# Motor_Driver_Mike.net
KiCad netlist of a schematic drawn in EAGLE
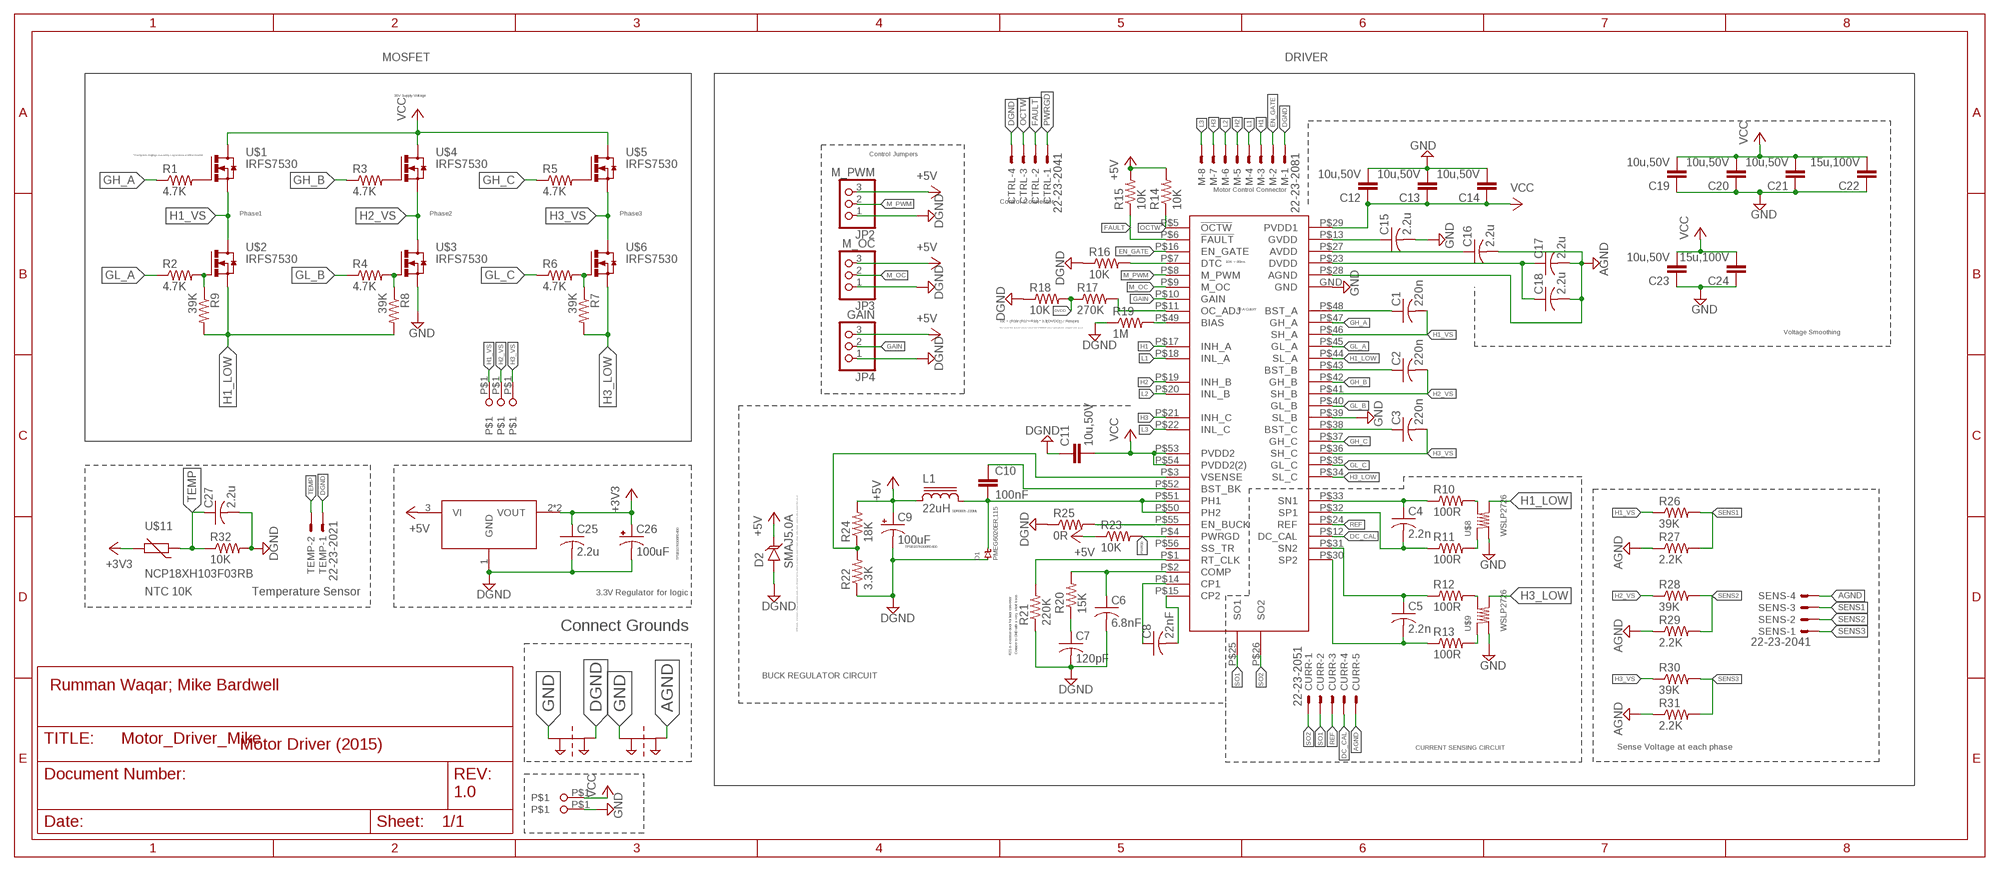
[diagram p0: schematic, sheet 1]

(export (version "E")
  (design (tool "Eeschema 10.0.6"))
  (components
    (comp (ref "C1")
      (value "220n")
      (footprint "eagle-import:C0805")
      (libsource (lib "eagle-import") (part "C-USC0805"))
    )
    (comp (ref "C2")
      (value "220n")
      (footprint "eagle-import:C0805")
      (libsource (lib "eagle-import") (part "C-USC0805"))
    )
    (comp (ref "C3")
      (value "220n")
      (footprint "eagle-import:C0805")
      (libsource (lib "eagle-import") (part "C-USC0805"))
    )
    (comp (ref "C4")
      (value "2.2n")
      (footprint "eagle-import:C0603")
      (libsource (lib "eagle-import") (part "C-USC0603"))
    )
    (comp (ref "C5")
      (value "2.2n")
      (footprint "eagle-import:C0603")
      (libsource (lib "eagle-import") (part "C-USC0603"))
    )
    (comp (ref "C6")
      (value "6.8nF")
      (footprint "eagle-import:C0603")
      (libsource (lib "eagle-import") (part "C-USC0603"))
    )
    (comp (ref "C7")
      (value "120pF")
      (footprint "eagle-import:C0603")
      (libsource (lib "eagle-import") (part "C-USC0603"))
    )
    (comp (ref "C8")
      (value "22nF")
      (footprint "eagle-import:C0603")
      (libsource (lib "eagle-import") (part "C-USC0603"))
    )
    (comp (ref "C9")
      (value "100uF")
      (footprint "eagle-import:EIA3528-KIT")
      (libsource (lib "eagle-import") (part "CAP_POL3528-KIT"))
    )
    (comp (ref "C10")
      (value "100nF")
      (footprint "eagle-import:0805")
      (libsource (lib "eagle-import") (part "CAP0805"))
    )
    (comp (ref "C11")
      (value "10u,50V")
      (footprint "eagle-import:1206")
      (libsource (lib "eagle-import") (part "CAP1206"))
    )
    (comp (ref "C12")
      (value "10u,50V")
      (footprint "eagle-import:1206")
      (libsource (lib "eagle-import") (part "CAP1206"))
    )
    (comp (ref "C13")
      (value "10u,50V")
      (footprint "eagle-import:1206")
      (libsource (lib "eagle-import") (part "CAP1206"))
    )
    (comp (ref "C14")
      (value "10u,50V")
      (footprint "eagle-import:1206")
      (libsource (lib "eagle-import") (part "CAP1206"))
    )
    (comp (ref "C15")
      (value "2.2u")
      (footprint "eagle-import:C0805")
      (libsource (lib "eagle-import") (part "C-USC0805"))
    )
    (comp (ref "C16")
      (value "2.2u")
      (footprint "eagle-import:C0805")
      (libsource (lib "eagle-import") (part "C-USC0805"))
    )
    (comp (ref "C17")
      (value "2.2u")
      (footprint "eagle-import:C0805")
      (libsource (lib "eagle-import") (part "C-USC0805"))
    )
    (comp (ref "C18")
      (value "2.2u")
      (footprint "eagle-import:C0805")
      (libsource (lib "eagle-import") (part "C-USC0805"))
    )
    (comp (ref "C19")
      (value "10u,50V")
      (footprint "eagle-import:1206")
      (libsource (lib "eagle-import") (part "CAP1206"))
    )
    (comp (ref "C20")
      (value "10u,50V")
      (footprint "eagle-import:1206")
      (libsource (lib "eagle-import") (part "CAP1206"))
    )
    (comp (ref "C21")
      (value "10u,50V")
      (footprint "eagle-import:1206")
      (libsource (lib "eagle-import") (part "CAP1206"))
    )
    (comp (ref "C22")
      (value "15u,100V")
      (footprint "eagle-import:C2220K")
      (libsource (lib "eagle-import") (part "C-EUC2220K"))
    )
    (comp (ref "C23")
      (value "10u,50V")
      (footprint "eagle-import:1206")
      (libsource (lib "eagle-import") (part "CAP1206"))
    )
    (comp (ref "C24")
      (value "15u,100V")
      (footprint "eagle-import:C2220K")
      (libsource (lib "eagle-import") (part "C-EUC2220K"))
    )
    (comp (ref "C25")
      (value "2.2u")
      (footprint "eagle-import:C0805")
      (libsource (lib "eagle-import") (part "C-USC0805"))
    )
    (comp (ref "C26")
      (value "100uF")
      (footprint "eagle-import:EIA3528-KIT")
      (libsource (lib "eagle-import") (part "CAP_POL3528-KIT"))
    )
    (comp (ref "C27")
      (value "2.2u")
      (footprint "eagle-import:C0805")
      (libsource (lib "eagle-import") (part "C-USC0805"))
    )
    (comp (ref "CTRL")
      (value "22-23-2041")
      (footprint "eagle-import:22-23-2041")
      (fields (field (name "MF") "MOLEX"))
      (libsource (lib "eagle-import") (part "22-23-2041"))
    )
    (comp (ref "CURR")
      (value "22-23-2051")
      (footprint "eagle-import:22-23-2051")
      (fields (field (name "MF") "MOLEX"))
      (libsource (lib "eagle-import") (part "22-23-2051"))
    )
    (comp (ref "D1")
      (value "PMEG6020ER,115")
      (footprint "eagle-import:SOD123W")
      (libsource (lib "eagle-import") (part "DIODE[SCHOTKY]-SOD123W"))
    )
    (comp (ref "D2")
      (value "SMAJ5.0A")
      (footprint "eagle-import:SMA-DIODE")
      (libsource (lib "eagle-import") (part "TVSSMA"))
    )
    (comp (ref "JP2")
      (value "M_PWM")
      (footprint "eagle-import:1X03")
      (libsource (lib "eagle-import") (part "PINHD-1X3"))
    )
    (comp (ref "JP3")
      (value "M_OC")
      (footprint "eagle-import:1X03")
      (libsource (lib "eagle-import") (part "PINHD-1X3"))
    )
    (comp (ref "JP4")
      (value "GAIN")
      (footprint "eagle-import:1X03")
      (libsource (lib "eagle-import") (part "PINHD-1X3"))
    )
    (comp (ref "L1")
      (value "22uH")
      (footprint "eagle-import:SDR0805")
      (libsource (lib "eagle-import") (part "SDR0805"))
    )
    (comp (ref "M")
      (value "22-23-2081")
      (footprint "eagle-import:22-23-2081")
      (fields (field (name "MF") "MOLEX"))
      (libsource (lib "eagle-import") (part "22-23-2081"))
    )
    (comp (ref "PT1")
      (value "2PT_GND_TIE")
      (footprint "eagle-import:2PT_GND_TIE")
      (libsource (lib "eagle-import") (part "2PT_GND_TIE"))
    )
    (comp (ref "PT2")
      (value "2PT_GND_TIE")
      (footprint "eagle-import:2PT_GND_TIE")
      (libsource (lib "eagle-import") (part "2PT_GND_TIE"))
    )
    (comp (ref "R1")
      (value "4.7K")
      (footprint "eagle-import:R0603")
      (libsource (lib "eagle-import") (part "R-US_R0603"))
    )
    (comp (ref "R2")
      (value "4.7K")
      (footprint "eagle-import:R0603")
      (libsource (lib "eagle-import") (part "R-US_R0603"))
    )
    (comp (ref "R3")
      (value "4.7K")
      (footprint "eagle-import:R0603")
      (libsource (lib "eagle-import") (part "R-US_R0603"))
    )
    (comp (ref "R4")
      (value "4.7K")
      (footprint "eagle-import:R0603")
      (libsource (lib "eagle-import") (part "R-US_R0603"))
    )
    (comp (ref "R5")
      (value "4.7K")
      (footprint "eagle-import:R0603")
      (libsource (lib "eagle-import") (part "R-US_R0603"))
    )
    (comp (ref "R6")
      (value "4.7K")
      (footprint "eagle-import:R0603")
      (libsource (lib "eagle-import") (part "R-US_R0603"))
    )
    (comp (ref "R7")
      (value "39K")
      (footprint "eagle-import:R0603")
      (libsource (lib "eagle-import") (part "R-US_R0603"))
    )
    (comp (ref "R8")
      (value "39K")
      (footprint "eagle-import:R0603")
      (libsource (lib "eagle-import") (part "R-US_R0603"))
    )
    (comp (ref "R9")
      (value "39K")
      (footprint "eagle-import:R0603")
      (libsource (lib "eagle-import") (part "R-US_R0603"))
    )
    (comp (ref "R10")
      (value "100R")
      (footprint "eagle-import:R0603")
      (libsource (lib "eagle-import") (part "R-US_R0603"))
    )
    (comp (ref "R11")
      (value "100R")
      (footprint "eagle-import:R0603")
      (libsource (lib "eagle-import") (part "R-US_R0603"))
    )
    (comp (ref "R12")
      (value "100R")
      (footprint "eagle-import:R0603")
      (libsource (lib "eagle-import") (part "R-US_R0603"))
    )
    (comp (ref "R13")
      (value "100R")
      (footprint "eagle-import:R0603")
      (libsource (lib "eagle-import") (part "R-US_R0603"))
    )
    (comp (ref "R14")
      (value "10K")
      (footprint "eagle-import:R0603")
      (libsource (lib "eagle-import") (part "R-US_R0603"))
    )
    (comp (ref "R15")
      (value "10K")
      (footprint "eagle-import:R0603")
      (libsource (lib "eagle-import") (part "R-US_R0603"))
    )
    (comp (ref "R16")
      (value "10K")
      (footprint "eagle-import:R0603")
      (libsource (lib "eagle-import") (part "R-US_R0603"))
    )
    (comp (ref "R17")
      (value "270K")
      (footprint "eagle-import:R0603")
      (libsource (lib "eagle-import") (part "R-US_R0603"))
    )
    (comp (ref "R18")
      (value "10K")
      (footprint "eagle-import:R0603")
      (libsource (lib "eagle-import") (part "R-US_R0603"))
    )
    (comp (ref "R19")
      (value "1M")
      (footprint "eagle-import:R0603")
      (libsource (lib "eagle-import") (part "R-US_R0603"))
    )
    (comp (ref "R20")
      (value "15K")
      (footprint "eagle-import:R0603")
      (libsource (lib "eagle-import") (part "R-US_R0603"))
    )
    (comp (ref "R21")
      (value "220K")
      (footprint "eagle-import:R0603")
      (libsource (lib "eagle-import") (part "R-US_R0603"))
    )
    (comp (ref "R22")
      (value "3.3K")
      (footprint "eagle-import:R0603")
      (libsource (lib "eagle-import") (part "R-US_R0603"))
    )
    (comp (ref "R23")
      (value "10K")
      (footprint "eagle-import:R0603")
      (libsource (lib "eagle-import") (part "R-US_R0603"))
    )
    (comp (ref "R24")
      (value "18K")
      (footprint "eagle-import:R0603")
      (libsource (lib "eagle-import") (part "R-US_R0603"))
    )
    (comp (ref "R25")
      (value "0R")
      (footprint "eagle-import:R0603")
      (libsource (lib "eagle-import") (part "R-US_R0603"))
    )
    (comp (ref "R26")
      (value "39K")
      (footprint "eagle-import:R0805")
      (libsource (lib "eagle-import") (part "R-US_R0805"))
    )
    (comp (ref "R27")
      (value "2.2K")
      (footprint "eagle-import:R0805")
      (libsource (lib "eagle-import") (part "R-US_R0805"))
    )
    (comp (ref "R28")
      (value "39K")
      (footprint "eagle-import:R0805")
      (libsource (lib "eagle-import") (part "R-US_R0805"))
    )
    (comp (ref "R29")
      (value "2.2K")
      (footprint "eagle-import:R0805")
      (libsource (lib "eagle-import") (part "R-US_R0805"))
    )
    (comp (ref "R30")
      (value "39K")
      (footprint "eagle-import:R0805")
      (libsource (lib "eagle-import") (part "R-US_R0805"))
    )
    (comp (ref "R31")
      (value "2.2K")
      (footprint "eagle-import:R0805")
      (libsource (lib "eagle-import") (part "R-US_R0805"))
    )
    (comp (ref "R32")
      (value "10K")
      (footprint "eagle-import:M0805")
      (libsource (lib "eagle-import") (part "R-US_M0805"))
    )
    (comp (ref "SENS")
      (value "22-23-2041")
      (footprint "eagle-import:22-23-2041")
      (fields (field (name "MF") "MOLEX"))
      (libsource (lib "eagle-import") (part "22-23-2041"))
    )
    (comp (ref "TEMP")
      (value "22-23-2021")
      (footprint "eagle-import:22-23-2021")
      (fields (field (name "MF") "MOLEX"))
      (libsource (lib "eagle-import") (part "22-23-2021"))
    )
    (comp (ref "U$1")
      (value "IRFS7530")
      (footprint "eagle-import:IRF7530_HEATSINK")
      (libsource (lib "eagle-import") (part "IRFS7530_HEATSINK"))
    )
    (comp (ref "U$2")
      (value "IRFS7530")
      (footprint "eagle-import:IRF7530_HEATSINK")
      (libsource (lib "eagle-import") (part "IRFS7530_HEATSINK"))
    )
    (comp (ref "U$3")
      (value "IRFS7530")
      (footprint "eagle-import:IRF7530_HEATSINK")
      (libsource (lib "eagle-import") (part "IRFS7530_HEATSINK"))
    )
    (comp (ref "U$4")
      (value "IRFS7530")
      (footprint "eagle-import:IRF7530_HEATSINK")
      (libsource (lib "eagle-import") (part "IRFS7530_HEATSINK"))
    )
    (comp (ref "U$5")
      (value "IRFS7530")
      (footprint "eagle-import:IRF7530_HEATSINK")
      (libsource (lib "eagle-import") (part "IRFS7530_HEATSINK"))
    )
    (comp (ref "U$6")
      (value "IRFS7530")
      (footprint "eagle-import:IRF7530_HEATSINK")
      (libsource (lib "eagle-import") (part "IRFS7530_HEATSINK"))
    )
    (comp (ref "U$7")
      (value "DRV8302")
      (footprint "eagle-import:DRV8302")
      (libsource (lib "eagle-import") (part "DRV8302"))
    )
    (comp (ref "U$8")
      (value "WSLP2726")
      (footprint "eagle-import:WSLP2726")
      (libsource (lib "eagle-import") (part "WSLP2726"))
    )
    (comp (ref "U$9")
      (value "WSLP2726")
      (footprint "eagle-import:WSLP2726")
      (libsource (lib "eagle-import") (part "WSLP2726"))
    )
    (comp (ref "U$10")
      (value "TC2117")
      (footprint "eagle-import:SOT223")
      (libsource (lib "eagle-import") (part "TC2117"))
    )
    (comp (ref "U$11")
      (value "NCP18XH103F03RB")
      (footprint "eagle-import:R0603")
      (libsource (lib "eagle-import") (part "NCP18XH103F03RB"))
    )
    (comp (ref "U$12")
      (value "1CONN_SOLDER")
      (footprint "eagle-import:1CONN_PAD")
      (libsource (lib "eagle-import") (part "1CONN_SOLDER"))
    )
    (comp (ref "U$13")
      (value "1CONN_SOLDER")
      (footprint "eagle-import:1CONN_PAD")
      (libsource (lib "eagle-import") (part "1CONN_SOLDER"))
    )
    (comp (ref "U$14")
      (value "1CONN_SOLDER")
      (footprint "eagle-import:1CONN_PAD")
      (libsource (lib "eagle-import") (part "1CONN_SOLDER"))
    )
    (comp (ref "U$15")
      (value "1CONN_SOLDER")
      (footprint "eagle-import:1CONN_PAD")
      (libsource (lib "eagle-import") (part "1CONN_SOLDER"))
    )
    (comp (ref "U$16")
      (value "1CONN_SOLDER")
      (footprint "eagle-import:1CONN_PAD")
      (libsource (lib "eagle-import") (part "1CONN_SOLDER"))
    )
  )
  (nets
    (net (code "1") (name "+3V3") (class "Default")
      (node (ref "C25") (pin "1") (pinfunction "1_1") (pintype "passive"))
      (node (ref "C26") (pin "A") (pinfunction "+_A") (pintype "passive"))
      (node (ref "U$10") (pin "2") (pinfunction "VOUT_2") (pintype "bidirectional"))
      (node (ref "U$10") (pin "4") (pinfunction "VOUT_4") (pintype "bidirectional"))
      (node (ref "U$11") (pin "2") (pinfunction "2_2") (pintype "passive"))
    )
    (net (code "2") (name "+5V") (class "Default")
      (node (ref "C9") (pin "A") (pinfunction "+_A") (pintype "passive"))
      (node (ref "D2") (pin "C") (pinfunction "C_C") (pintype "passive"))
      (node (ref "JP2") (pin "3") (pinfunction "3_3") (pintype "passive"))
      (node (ref "JP3") (pin "3") (pinfunction "3_3") (pintype "passive"))
      (node (ref "JP4") (pin "3") (pinfunction "3_3") (pintype "passive"))
      (node (ref "L1") (pin "1") (pinfunction "1_1") (pintype "passive"))
      (node (ref "R14") (pin "2") (pinfunction "2_2") (pintype "passive"))
      (node (ref "R15") (pin "2") (pinfunction "2_2") (pintype "passive"))
      (node (ref "R23") (pin "1") (pinfunction "1_1") (pintype "passive"))
      (node (ref "R24") (pin "2") (pinfunction "2_2") (pintype "passive"))
      (node (ref "U$10") (pin "3") (pinfunction "VI_3") (pintype "bidirectional"))
    )
    (net (code "3") (name "AGND") (class "Default")
      (node (ref "C16") (pin "2") (pinfunction "2_2") (pintype "passive"))
      (node (ref "C17") (pin "2") (pinfunction "2_2") (pintype "passive"))
      (node (ref "C18") (pin "2") (pinfunction "2_2") (pintype "passive"))
      (node (ref "CURR") (pin "5") (pinfunction "S_5") (pintype "passive"))
      (node (ref "PT2") (pin "P$2") (pinfunction "P$2_P$2") (pintype "bidirectional"))
      (node (ref "R27") (pin "1") (pinfunction "1_1") (pintype "passive"))
      (node (ref "R29") (pin "1") (pinfunction "1_1") (pintype "passive"))
      (node (ref "R31") (pin "1") (pinfunction "1_1") (pintype "passive"))
      (node (ref "SENS") (pin "4") (pinfunction "S_4") (pintype "passive"))
      (node (ref "U$7") (pin "P$28") (pinfunction "AGND_P$28") (pintype "bidirectional"))
    )
    (net (code "4") (name "DC_CAL") (class "Default")
      (node (ref "CURR") (pin "4") (pinfunction "S_4") (pintype "passive"))
      (node (ref "U$7") (pin "P$12") (pinfunction "DC_CAL_P$12") (pintype "bidirectional"))
    )
    (net (code "5") (name "DGND") (class "Default")
      (node (ref "C11") (pin "1") (pinfunction "1_1") (pintype "passive"))
      (node (ref "C25") (pin "2") (pinfunction "2_2") (pintype "passive"))
      (node (ref "C26") (pin "C") (pinfunction "-_C") (pintype "passive"))
      (node (ref "C27") (pin "2") (pinfunction "2_2") (pintype "passive"))
      (node (ref "C6") (pin "2") (pinfunction "2_2") (pintype "passive"))
      (node (ref "C7") (pin "2") (pinfunction "2_2") (pintype "passive"))
      (node (ref "C9") (pin "C") (pinfunction "-_C") (pintype "passive"))
      (node (ref "CTRL") (pin "4") (pinfunction "S_4") (pintype "passive"))
      (node (ref "D1") (pin "P$1") (pinfunction "1_P$1") (pintype "bidirectional"))
      (node (ref "D2") (pin "A") (pinfunction "A_A") (pintype "passive"))
      (node (ref "JP2") (pin "1") (pinfunction "1_1") (pintype "passive"))
      (node (ref "JP3") (pin "1") (pinfunction "1_1") (pintype "passive"))
      (node (ref "JP4") (pin "1") (pinfunction "1_1") (pintype "passive"))
      (node (ref "M") (pin "1") (pinfunction "S_1") (pintype "passive"))
      (node (ref "PT1") (pin "P$2") (pinfunction "P$2_P$2") (pintype "bidirectional"))
      (node (ref "R16") (pin "1") (pinfunction "1_1") (pintype "passive"))
      (node (ref "R18") (pin "1") (pinfunction "1_1") (pintype "passive"))
      (node (ref "R19") (pin "1") (pinfunction "1_1") (pintype "passive"))
      (node (ref "R21") (pin "1") (pinfunction "1_1") (pintype "passive"))
      (node (ref "R22") (pin "1") (pinfunction "1_1") (pintype "passive"))
      (node (ref "R25") (pin "1") (pinfunction "1_1") (pintype "passive"))
      (node (ref "R32") (pin "2") (pinfunction "2_2") (pintype "passive"))
      (node (ref "TEMP") (pin "1") (pinfunction "S_1") (pintype "passive"))
      (node (ref "U$10") (pin "1") (pinfunction "GND_1") (pintype "bidirectional"))
    )
    (net (code "6") (name "DVDD") (class "Default")
      (node (ref "R17") (pin "1") (pinfunction "1_1") (pintype "passive"))
      (node (ref "R18") (pin "2") (pinfunction "2_2") (pintype "passive"))
    )
    (net (code "7") (name "EN_GATE") (class "Default")
      (node (ref "M") (pin "2") (pinfunction "S_2") (pintype "passive"))
      (node (ref "U$7") (pin "P$16") (pinfunction "EN_GATE_P$16") (pintype "bidirectional"))
    )
    (net (code "8") (name "FAULT") (class "Default")
      (node (ref "CTRL") (pin "2") (pinfunction "S_2") (pintype "passive"))
      (node (ref "R15") (pin "1") (pinfunction "1_1") (pintype "passive"))
      (node (ref "U$7") (pin "P$6") (pinfunction "~{FAULT}_P$6") (pintype "bidirectional"))
    )
    (net (code "9") (name "GAIN") (class "Default")
      (node (ref "JP4") (pin "2") (pinfunction "2_2") (pintype "passive"))
      (node (ref "U$7") (pin "P$10") (pinfunction "GAIN_P$10") (pintype "bidirectional"))
    )
    (net (code "10") (name "GH_A") (class "Default")
      (node (ref "R1") (pin "1") (pinfunction "1_1") (pintype "passive"))
      (node (ref "U$7") (pin "P$47") (pinfunction "GH_A_P$47") (pintype "bidirectional"))
    )
    (net (code "11") (name "GH_B") (class "Default")
      (node (ref "R3") (pin "1") (pinfunction "1_1") (pintype "passive"))
      (node (ref "U$7") (pin "P$42") (pinfunction "GH_B_P$42") (pintype "bidirectional"))
    )
    (net (code "12") (name "GH_C") (class "Default")
      (node (ref "R5") (pin "1") (pinfunction "1_1") (pintype "passive"))
      (node (ref "U$7") (pin "P$37") (pinfunction "GH_C_P$37") (pintype "bidirectional"))
    )
    (net (code "13") (name "GL_A") (class "Default")
      (node (ref "R2") (pin "1") (pinfunction "1_1") (pintype "passive"))
      (node (ref "U$7") (pin "P$45") (pinfunction "GL_A_P$45") (pintype "bidirectional"))
    )
    (net (code "14") (name "GL_B") (class "Default")
      (node (ref "R4") (pin "1") (pinfunction "1_1") (pintype "passive"))
      (node (ref "U$7") (pin "P$40") (pinfunction "GL_B_P$40") (pintype "bidirectional"))
    )
    (net (code "15") (name "GL_C") (class "Default")
      (node (ref "R6") (pin "1") (pinfunction "1_1") (pintype "passive"))
      (node (ref "U$7") (pin "P$35") (pinfunction "GL_C_P$35") (pintype "bidirectional"))
    )
    (net (code "16") (name "GND") (class "Default")
      (node (ref "C12") (pin "2") (pinfunction "2_2") (pintype "passive"))
      (node (ref "C13") (pin "2") (pinfunction "2_2") (pintype "passive"))
      (node (ref "C14") (pin "2") (pinfunction "2_2") (pintype "passive"))
      (node (ref "C15") (pin "2") (pinfunction "2_2") (pintype "passive"))
      (node (ref "C19") (pin "1") (pinfunction "1_1") (pintype "passive"))
      (node (ref "C20") (pin "1") (pinfunction "1_1") (pintype "passive"))
      (node (ref "C21") (pin "1") (pinfunction "1_1") (pintype "passive"))
      (node (ref "C22") (pin "1") (pinfunction "1_1") (pintype "passive"))
      (node (ref "C23") (pin "1") (pinfunction "1_1") (pintype "passive"))
      (node (ref "C24") (pin "1") (pinfunction "1_1") (pintype "passive"))
      (node (ref "PT1") (pin "P$1") (pinfunction "P$1_P$1") (pintype "bidirectional"))
      (node (ref "PT2") (pin "P$1") (pinfunction "P$1_P$1") (pintype "bidirectional"))
      (node (ref "U$16") (pin "P$1") (pinfunction "P$1_P$1") (pintype "bidirectional"))
      (node (ref "U$3") (pin "S1") (pinfunction "S_S1") (pintype "passive"))
      (node (ref "U$3") (pin "S2") (pinfunction "S_S2") (pintype "passive"))
      (node (ref "U$3") (pin "S3") (pinfunction "S_S3") (pintype "passive"))
      (node (ref "U$3") (pin "S4") (pinfunction "S_S4") (pintype "passive"))
      (node (ref "U$3") (pin "S5") (pinfunction "S_S5") (pintype "passive"))
      (node (ref "U$7") (pin "GND") (pinfunction "GND_GND") (pintype "bidirectional"))
      (node (ref "U$7") (pin "P$39") (pinfunction "SL_B_P$39") (pintype "bidirectional"))
      (node (ref "U$8") (pin "P$2") (pinfunction "P$2_P$2") (pintype "bidirectional"))
      (node (ref "U$9") (pin "P$2") (pinfunction "P$2_P$2") (pintype "bidirectional"))
    )
    (net (code "17") (name "H1") (class "Default")
      (node (ref "M") (pin "3") (pinfunction "S_3") (pintype "passive"))
      (node (ref "U$7") (pin "P$17") (pinfunction "INH_A_P$17") (pintype "bidirectional"))
    )
    (net (code "18") (name "H1_LOW") (class "Default")
      (node (ref "R8") (pin "2") (pinfunction "2_2") (pintype "passive"))
      (node (ref "R9") (pin "2") (pinfunction "2_2") (pintype "passive"))
      (node (ref "U$2") (pin "S1") (pinfunction "S_S1") (pintype "passive"))
      (node (ref "U$2") (pin "S2") (pinfunction "S_S2") (pintype "passive"))
      (node (ref "U$2") (pin "S3") (pinfunction "S_S3") (pintype "passive"))
      (node (ref "U$2") (pin "S4") (pinfunction "S_S4") (pintype "passive"))
      (node (ref "U$2") (pin "S5") (pinfunction "S_S5") (pintype "passive"))
      (node (ref "U$7") (pin "P$44") (pinfunction "SL_A_P$44") (pintype "bidirectional"))
      (node (ref "U$8") (pin "P$1") (pinfunction "P$1_P$1") (pintype "bidirectional"))
    )
    (net (code "19") (name "H1_VS") (class "Default")
      (node (ref "C1") (pin "2") (pinfunction "2_2") (pintype "passive"))
      (node (ref "R26") (pin "1") (pinfunction "1_1") (pintype "passive"))
      (node (ref "U$1") (pin "S1") (pinfunction "S_S1") (pintype "passive"))
      (node (ref "U$1") (pin "S2") (pinfunction "S_S2") (pintype "passive"))
      (node (ref "U$1") (pin "S3") (pinfunction "S_S3") (pintype "passive"))
      (node (ref "U$1") (pin "S4") (pinfunction "S_S4") (pintype "passive"))
      (node (ref "U$1") (pin "S5") (pinfunction "S_S5") (pintype "passive"))
      (node (ref "U$14") (pin "P$1") (pinfunction "P$1_P$1") (pintype "bidirectional"))
      (node (ref "U$2") (pin "D1") (pinfunction "D_D1") (pintype "passive"))
      (node (ref "U$7") (pin "P$46") (pinfunction "SH_A_P$46") (pintype "bidirectional"))
    )
    (net (code "20") (name "H2") (class "Default")
      (node (ref "M") (pin "5") (pinfunction "S_5") (pintype "passive"))
      (node (ref "U$7") (pin "P$19") (pinfunction "INH_B_P$19") (pintype "bidirectional"))
    )
    (net (code "21") (name "H2_VS") (class "Default")
      (node (ref "C2") (pin "2") (pinfunction "2_2") (pintype "passive"))
      (node (ref "R28") (pin "1") (pinfunction "1_1") (pintype "passive"))
      (node (ref "U$13") (pin "P$1") (pinfunction "P$1_P$1") (pintype "bidirectional"))
      (node (ref "U$3") (pin "D1") (pinfunction "D_D1") (pintype "passive"))
      (node (ref "U$4") (pin "S1") (pinfunction "S_S1") (pintype "passive"))
      (node (ref "U$4") (pin "S2") (pinfunction "S_S2") (pintype "passive"))
      (node (ref "U$4") (pin "S3") (pinfunction "S_S3") (pintype "passive"))
      (node (ref "U$4") (pin "S4") (pinfunction "S_S4") (pintype "passive"))
      (node (ref "U$4") (pin "S5") (pinfunction "S_S5") (pintype "passive"))
      (node (ref "U$7") (pin "P$41") (pinfunction "SH_B_P$41") (pintype "bidirectional"))
    )
    (net (code "22") (name "H3") (class "Default")
      (node (ref "M") (pin "7") (pinfunction "S_7") (pintype "passive"))
      (node (ref "U$7") (pin "P$21") (pinfunction "INH_C_P$21") (pintype "bidirectional"))
    )
    (net (code "23") (name "H3_LOW") (class "Default")
      (node (ref "R7") (pin "2") (pinfunction "2_2") (pintype "passive"))
      (node (ref "U$6") (pin "S1") (pinfunction "S_S1") (pintype "passive"))
      (node (ref "U$6") (pin "S2") (pinfunction "S_S2") (pintype "passive"))
      (node (ref "U$6") (pin "S3") (pinfunction "S_S3") (pintype "passive"))
      (node (ref "U$6") (pin "S4") (pinfunction "S_S4") (pintype "passive"))
      (node (ref "U$6") (pin "S5") (pinfunction "S_S5") (pintype "passive"))
      (node (ref "U$7") (pin "P$34") (pinfunction "SL_C_P$34") (pintype "bidirectional"))
      (node (ref "U$9") (pin "P$1") (pinfunction "P$1_P$1") (pintype "bidirectional"))
    )
    (net (code "24") (name "H3_VS") (class "Default")
      (node (ref "C3") (pin "2") (pinfunction "2_2") (pintype "passive"))
      (node (ref "R30") (pin "1") (pinfunction "1_1") (pintype "passive"))
      (node (ref "U$12") (pin "P$1") (pinfunction "P$1_P$1") (pintype "bidirectional"))
      (node (ref "U$5") (pin "S1") (pinfunction "S_S1") (pintype "passive"))
      (node (ref "U$5") (pin "S2") (pinfunction "S_S2") (pintype "passive"))
      (node (ref "U$5") (pin "S3") (pinfunction "S_S3") (pintype "passive"))
      (node (ref "U$5") (pin "S4") (pinfunction "S_S4") (pintype "passive"))
      (node (ref "U$5") (pin "S5") (pinfunction "S_S5") (pintype "passive"))
      (node (ref "U$6") (pin "D1") (pinfunction "D_D1") (pintype "passive"))
      (node (ref "U$7") (pin "P$36") (pinfunction "SH_C_P$36") (pintype "bidirectional"))
    )
    (net (code "25") (name "L1") (class "Default")
      (node (ref "M") (pin "4") (pinfunction "S_4") (pintype "passive"))
      (node (ref "U$7") (pin "P$18") (pinfunction "INL_A_P$18") (pintype "bidirectional"))
    )
    (net (code "26") (name "L2") (class "Default")
      (node (ref "M") (pin "6") (pinfunction "S_6") (pintype "passive"))
      (node (ref "U$7") (pin "P$20") (pinfunction "INL_B_P$20") (pintype "bidirectional"))
    )
    (net (code "27") (name "L3") (class "Default")
      (node (ref "M") (pin "8") (pinfunction "S_8") (pintype "passive"))
      (node (ref "U$7") (pin "P$22") (pinfunction "INL_C_P$22") (pintype "bidirectional"))
    )
    (net (code "28") (name "M_OC") (class "Default")
      (node (ref "JP3") (pin "2") (pinfunction "2_2") (pintype "passive"))
      (node (ref "U$7") (pin "P$9") (pinfunction "M_OC_P$9") (pintype "bidirectional"))
    )
    (net (code "29") (name "M_PWM") (class "Default")
      (node (ref "JP2") (pin "2") (pinfunction "2_2") (pintype "passive"))
      (node (ref "U$7") (pin "P$8") (pinfunction "M_PWM_P$8") (pintype "bidirectional"))
    )
    (net (code "30") (name "Net-(C7-Pad1)") (class "Default")
      (node (ref "C7") (pin "1") (pinfunction "1_1") (pintype "passive"))
      (node (ref "R20") (pin "1") (pinfunction "1_1") (pintype "passive"))
    )
    (net (code "31") (name "Net-(D1-2)") (class "Default")
      (node (ref "C10") (pin "2") (pinfunction "2_2") (pintype "passive"))
      (node (ref "D1") (pin "P$2") (pinfunction "2_P$2") (pintype "bidirectional"))
      (node (ref "L1") (pin "2") (pinfunction "2_2") (pintype "passive"))
      (node (ref "U$7") (pin "P$50") (pinfunction "PH2_P$50") (pintype "bidirectional"))
      (node (ref "U$7") (pin "P$51") (pinfunction "PH1_P$51") (pintype "bidirectional"))
    )
    (net (code "32") (name "Net-(R10-Pad2)") (class "Default")
      (node (ref "R10") (pin "2") (pinfunction "2_2") (pintype "passive"))
      (node (ref "U$8") (pin "P$3") (pinfunction "P$3_P$3") (pintype "bidirectional"))
    )
    (net (code "33") (name "Net-(R11-Pad2)") (class "Default")
      (node (ref "R11") (pin "2") (pinfunction "2_2") (pintype "passive"))
      (node (ref "U$8") (pin "P$4") (pinfunction "P$4_P$4") (pintype "bidirectional"))
    )
    (net (code "34") (name "Net-(R12-Pad2)") (class "Default")
      (node (ref "R12") (pin "2") (pinfunction "2_2") (pintype "passive"))
      (node (ref "U$9") (pin "P$3") (pinfunction "P$3_P$3") (pintype "bidirectional"))
    )
    (net (code "35") (name "Net-(R13-Pad2)") (class "Default")
      (node (ref "R13") (pin "2") (pinfunction "2_2") (pintype "passive"))
      (node (ref "U$9") (pin "P$4") (pinfunction "P$4_P$4") (pintype "bidirectional"))
    )
    (net (code "36") (name "Net-(U$1-G)") (class "Default")
      (node (ref "R1") (pin "2") (pinfunction "2_2") (pintype "passive"))
      (node (ref "U$1") (pin "G1") (pinfunction "G_G1") (pintype "passive"))
    )
    (net (code "37") (name "Net-(U$2-G)") (class "Default")
      (node (ref "R2") (pin "2") (pinfunction "2_2") (pintype "passive"))
      (node (ref "R9") (pin "1") (pinfunction "1_1") (pintype "passive"))
      (node (ref "U$2") (pin "G1") (pinfunction "G_G1") (pintype "passive"))
    )
    (net (code "38") (name "Net-(U$3-G)") (class "Default")
      (node (ref "R4") (pin "2") (pinfunction "2_2") (pintype "passive"))
      (node (ref "R8") (pin "1") (pinfunction "1_1") (pintype "passive"))
      (node (ref "U$3") (pin "G1") (pinfunction "G_G1") (pintype "passive"))
    )
    (net (code "39") (name "Net-(U$4-G)") (class "Default")
      (node (ref "R3") (pin "2") (pinfunction "2_2") (pintype "passive"))
      (node (ref "U$4") (pin "G1") (pinfunction "G_G1") (pintype "passive"))
    )
    (net (code "40") (name "Net-(U$5-G)") (class "Default")
      (node (ref "R5") (pin "2") (pinfunction "2_2") (pintype "passive"))
      (node (ref "U$5") (pin "G1") (pinfunction "G_G1") (pintype "passive"))
    )
    (net (code "41") (name "Net-(U$6-G)") (class "Default")
      (node (ref "R6") (pin "2") (pinfunction "2_2") (pintype "passive"))
      (node (ref "R7") (pin "1") (pinfunction "1_1") (pintype "passive"))
      (node (ref "U$6") (pin "G1") (pinfunction "G_G1") (pintype "passive"))
    )
    (net (code "42") (name "Net-(U$7-AVDD)") (class "Default")
      (node (ref "C16") (pin "1") (pinfunction "1_1") (pintype "passive"))
      (node (ref "U$7") (pin "P$27") (pinfunction "AVDD_P$27") (pintype "bidirectional"))
    )
    (net (code "43") (name "Net-(U$7-BIAS)") (class "Default")
      (node (ref "R19") (pin "2") (pinfunction "2_2") (pintype "passive"))
      (node (ref "U$7") (pin "P$49") (pinfunction "BIAS_P$49") (pintype "bidirectional"))
    )
    (net (code "44") (name "Net-(U$7-BST_A)") (class "Default")
      (node (ref "C1") (pin "1") (pinfunction "1_1") (pintype "passive"))
      (node (ref "U$7") (pin "P$48") (pinfunction "BST_A_P$48") (pintype "bidirectional"))
    )
    (net (code "45") (name "Net-(U$7-BST_B)") (class "Default")
      (node (ref "C2") (pin "1") (pinfunction "1_1") (pintype "passive"))
      (node (ref "U$7") (pin "P$43") (pinfunction "BST_B_P$43") (pintype "bidirectional"))
    )
    (net (code "46") (name "Net-(U$7-BST_BK)") (class "Default")
      (node (ref "C10") (pin "1") (pinfunction "1_1") (pintype "passive"))
      (node (ref "U$7") (pin "P$52") (pinfunction "BST_BK_P$52") (pintype "bidirectional"))
    )
    (net (code "47") (name "Net-(U$7-BST_C)") (class "Default")
      (node (ref "C3") (pin "1") (pinfunction "1_1") (pintype "passive"))
      (node (ref "U$7") (pin "P$38") (pinfunction "BST_C_P$38") (pintype "bidirectional"))
    )
    (net (code "48") (name "Net-(U$7-COMP)") (class "Default")
      (node (ref "C6") (pin "1") (pinfunction "1_1") (pintype "passive"))
      (node (ref "R20") (pin "2") (pinfunction "2_2") (pintype "passive"))
      (node (ref "U$7") (pin "P$2") (pinfunction "COMP_P$2") (pintype "bidirectional"))
    )
    (net (code "49") (name "Net-(U$7-CP1)") (class "Default")
      (node (ref "C8") (pin "1") (pinfunction "1_1") (pintype "passive"))
      (node (ref "U$7") (pin "P$14") (pinfunction "CP1_P$14") (pintype "bidirectional"))
    )
    (net (code "50") (name "Net-(U$7-CP2)") (class "Default")
      (node (ref "C8") (pin "2") (pinfunction "2_2") (pintype "passive"))
      (node (ref "U$7") (pin "P$15") (pinfunction "CP2_P$15") (pintype "bidirectional"))
    )
    (net (code "51") (name "Net-(U$7-DTC)") (class "Default")
      (node (ref "R16") (pin "2") (pinfunction "2_2") (pintype "passive"))
      (node (ref "U$7") (pin "P$7") (pinfunction "DTC_P$7") (pintype "bidirectional"))
    )
    (net (code "52") (name "Net-(U$7-DVDD)") (class "Default")
      (node (ref "C17") (pin "1") (pinfunction "1_1") (pintype "passive"))
      (node (ref "C18") (pin "1") (pinfunction "1_1") (pintype "passive"))
      (node (ref "U$7") (pin "P$23") (pinfunction "DVDD_P$23") (pintype "bidirectional"))
    )
    (net (code "53") (name "Net-(U$7-EN_BUCK)") (class "Default")
      (node (ref "R25") (pin "2") (pinfunction "2_2") (pintype "passive"))
      (node (ref "U$7") (pin "P$55") (pinfunction "EN_BUCK_P$55") (pintype "bidirectional"))
    )
    (net (code "54") (name "Net-(U$7-GVDD)") (class "Default")
      (node (ref "C15") (pin "1") (pinfunction "1_1") (pintype "passive"))
      (node (ref "U$7") (pin "P$13") (pinfunction "GVDD_P$13") (pintype "bidirectional"))
    )
    (net (code "55") (name "Net-(U$7-OC_ADJ)") (class "Default")
      (node (ref "R17") (pin "2") (pinfunction "2_2") (pintype "passive"))
      (node (ref "U$7") (pin "P$11") (pinfunction "OC_ADJ_P$11") (pintype "bidirectional"))
    )
    (net (code "56") (name "Net-(U$7-RT_CLK)") (class "Default")
      (node (ref "R21") (pin "2") (pinfunction "2_2") (pintype "passive"))
      (node (ref "U$7") (pin "P$1") (pinfunction "RT_CLK_P$1") (pintype "bidirectional"))
    )
    (net (code "57") (name "Net-(U$7-SN1)") (class "Default")
      (node (ref "C4") (pin "1") (pinfunction "1_1") (pintype "passive"))
      (node (ref "R10") (pin "1") (pinfunction "1_1") (pintype "passive"))
      (node (ref "U$7") (pin "P$33") (pinfunction "SN1_P$33") (pintype "bidirectional"))
    )
    (net (code "58") (name "Net-(U$7-SN2)") (class "Default")
      (node (ref "C5") (pin "1") (pinfunction "1_1") (pintype "passive"))
      (node (ref "R12") (pin "1") (pinfunction "1_1") (pintype "passive"))
      (node (ref "U$7") (pin "P$31") (pinfunction "SN2_P$31") (pintype "bidirectional"))
    )
    (net (code "59") (name "Net-(U$7-SP1)") (class "Default")
      (node (ref "C4") (pin "2") (pinfunction "2_2") (pintype "passive"))
      (node (ref "R11") (pin "1") (pinfunction "1_1") (pintype "passive"))
      (node (ref "U$7") (pin "P$32") (pinfunction "SP1_P$32") (pintype "bidirectional"))
    )
    (net (code "60") (name "Net-(U$7-SP2)") (class "Default")
      (node (ref "C5") (pin "2") (pinfunction "2_2") (pintype "passive"))
      (node (ref "R13") (pin "1") (pinfunction "1_1") (pintype "passive"))
      (node (ref "U$7") (pin "P$30") (pinfunction "SP2_P$30") (pintype "bidirectional"))
    )
    (net (code "61") (name "Net-(U$7-VSENSE)") (class "Default")
      (node (ref "R22") (pin "2") (pinfunction "2_2") (pintype "passive"))
      (node (ref "R24") (pin "1") (pinfunction "1_1") (pintype "passive"))
      (node (ref "U$7") (pin "P$3") (pinfunction "VSENSE_P$3") (pintype "bidirectional"))
    )
    (net (code "62") (name "OCTW") (class "Default")
      (node (ref "CTRL") (pin "3") (pinfunction "S_3") (pintype "passive"))
      (node (ref "R14") (pin "1") (pinfunction "1_1") (pintype "passive"))
      (node (ref "U$7") (pin "P$5") (pinfunction "~{OCTW}_P$5") (pintype "bidirectional"))
    )
    (net (code "63") (name "PWRGD") (class "Default")
      (node (ref "CTRL") (pin "1") (pinfunction "S_1") (pintype "passive"))
      (node (ref "R23") (pin "2") (pinfunction "2_2") (pintype "passive"))
      (node (ref "U$7") (pin "P$4") (pinfunction "PWRGD_P$4") (pintype "bidirectional"))
    )
    (net (code "64") (name "REF") (class "Default")
      (node (ref "CURR") (pin "3") (pinfunction "S_3") (pintype "passive"))
      (node (ref "U$7") (pin "P$24") (pinfunction "REF_P$24") (pintype "bidirectional"))
    )
    (net (code "65") (name "SENS1") (class "Default")
      (node (ref "R26") (pin "2") (pinfunction "2_2") (pintype "passive"))
      (node (ref "R27") (pin "2") (pinfunction "2_2") (pintype "passive"))
      (node (ref "SENS") (pin "3") (pinfunction "S_3") (pintype "passive"))
    )
    (net (code "66") (name "SENS2") (class "Default")
      (node (ref "R28") (pin "2") (pinfunction "2_2") (pintype "passive"))
      (node (ref "R29") (pin "2") (pinfunction "2_2") (pintype "passive"))
      (node (ref "SENS") (pin "2") (pinfunction "S_2") (pintype "passive"))
    )
    (net (code "67") (name "SENS3") (class "Default")
      (node (ref "R30") (pin "2") (pinfunction "2_2") (pintype "passive"))
      (node (ref "R31") (pin "2") (pinfunction "2_2") (pintype "passive"))
      (node (ref "SENS") (pin "1") (pinfunction "S_1") (pintype "passive"))
    )
    (net (code "68") (name "SO1") (class "Default")
      (node (ref "CURR") (pin "2") (pinfunction "S_2") (pintype "passive"))
      (node (ref "U$7") (pin "P$25") (pinfunction "SO1_P$25") (pintype "bidirectional"))
    )
    (net (code "69") (name "SO2") (class "Default")
      (node (ref "CURR") (pin "1") (pinfunction "S_1") (pintype "passive"))
      (node (ref "U$7") (pin "P$26") (pinfunction "SO2_P$26") (pintype "bidirectional"))
    )
    (net (code "70") (name "TEMP") (class "Default")
      (node (ref "C27") (pin "1") (pinfunction "1_1") (pintype "passive"))
      (node (ref "R32") (pin "1") (pinfunction "1_1") (pintype "passive"))
      (node (ref "TEMP") (pin "2") (pinfunction "S_2") (pintype "passive"))
      (node (ref "U$11") (pin "1") (pinfunction "1_1") (pintype "passive"))
    )
    (net (code "71") (name "VCC") (class "Default")
      (node (ref "C11") (pin "2") (pinfunction "2_2") (pintype "passive"))
      (node (ref "C12") (pin "1") (pinfunction "1_1") (pintype "passive"))
      (node (ref "C13") (pin "1") (pinfunction "1_1") (pintype "passive"))
      (node (ref "C14") (pin "1") (pinfunction "1_1") (pintype "passive"))
      (node (ref "C19") (pin "2") (pinfunction "2_2") (pintype "passive"))
      (node (ref "C20") (pin "2") (pinfunction "2_2") (pintype "passive"))
      (node (ref "C21") (pin "2") (pinfunction "2_2") (pintype "passive"))
      (node (ref "C22") (pin "2") (pinfunction "2_2") (pintype "passive"))
      (node (ref "C23") (pin "2") (pinfunction "2_2") (pintype "passive"))
      (node (ref "C24") (pin "2") (pinfunction "2_2") (pintype "passive"))
      (node (ref "U$1") (pin "D1") (pinfunction "D_D1") (pintype "passive"))
      (node (ref "U$15") (pin "P$1") (pinfunction "P$1_P$1") (pintype "bidirectional"))
      (node (ref "U$4") (pin "D1") (pinfunction "D_D1") (pintype "passive"))
      (node (ref "U$5") (pin "D1") (pinfunction "D_D1") (pintype "passive"))
      (node (ref "U$7") (pin "P$29") (pinfunction "PVDD1_P$29") (pintype "bidirectional"))
      (node (ref "U$7") (pin "P$53") (pinfunction "PVDD2_P$53") (pintype "bidirectional"))
      (node (ref "U$7") (pin "P$54") (pinfunction "PVDD2(2)_P$54") (pintype "bidirectional"))
    )
    (net (code "72") (name "unconnected-(U$7-SS_TR-PadP$56)") (class "Default")
      (node (ref "U$7") (pin "P$56") (pinfunction "SS_TR_P$56") (pintype "bidirectional"))
    )
  )
)
